# ultrasonic-breakout-smd.net
KiCad netlist of a schematic drawn in EAGLE
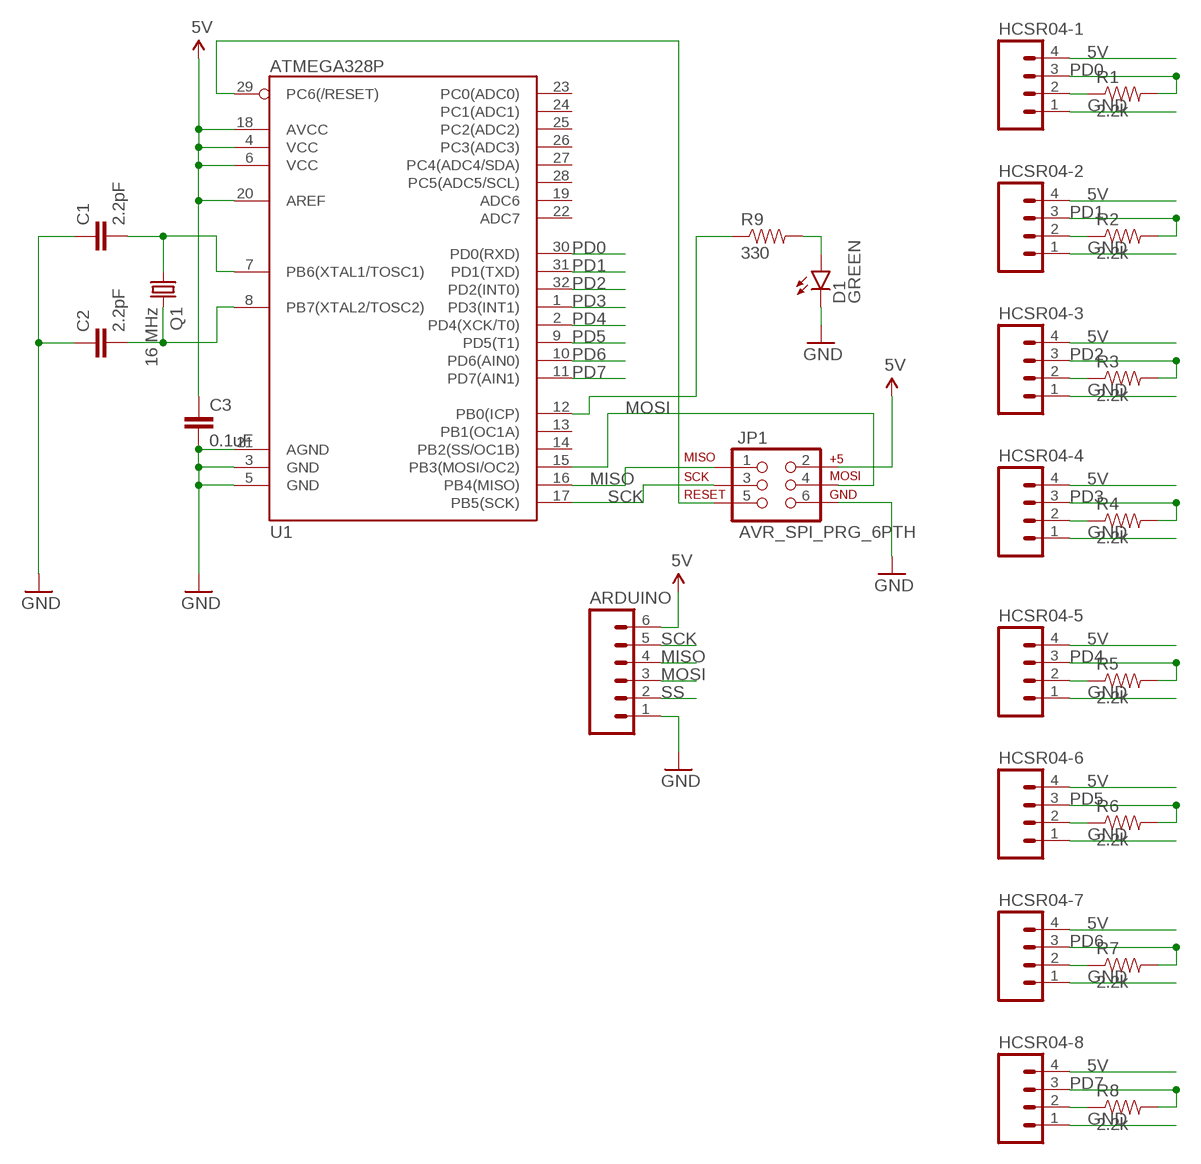
[diagram p0: schematic, sheet 1]

(export (version "E")
  (design (tool "Eeschema 10.0.6"))
  (components
    (comp (ref "ARDUINO")
      (value "M06LOCK")
      (footprint "eagle-import:1X06_LOCK")
      (libsource (lib "eagle-import") (part "M06LOCK"))
    )
    (comp (ref "C1")
      (value "2.2pF")
      (footprint "eagle-import:0402-CAP")
      (libsource (lib "eagle-import") (part "CAP0402-CAP"))
    )
    (comp (ref "C2")
      (value "2.2pF")
      (footprint "eagle-import:0402-CAP")
      (libsource (lib "eagle-import") (part "CAP0402-CAP"))
    )
    (comp (ref "C3")
      (value "0.1uF")
      (footprint "eagle-import:0402-CAP")
      (libsource (lib "eagle-import") (part "CAP0402-CAP"))
    )
    (comp (ref "D1")
      (value "GREEN")
      (footprint "eagle-import:LED-0603")
      (libsource (lib "eagle-import") (part "LED-GREEN0603"))
    )
    (comp (ref "HCSR04-1")
      (value "M04PTH")
      (footprint "eagle-import:1X04")
      (libsource (lib "eagle-import") (part "M04PTH"))
    )
    (comp (ref "HCSR04-2")
      (value "M04PTH")
      (footprint "eagle-import:1X04")
      (libsource (lib "eagle-import") (part "M04PTH"))
    )
    (comp (ref "HCSR04-3")
      (value "M04PTH")
      (footprint "eagle-import:1X04")
      (libsource (lib "eagle-import") (part "M04PTH"))
    )
    (comp (ref "HCSR04-4")
      (value "M04PTH")
      (footprint "eagle-import:1X04")
      (libsource (lib "eagle-import") (part "M04PTH"))
    )
    (comp (ref "HCSR04-5")
      (value "M04PTH")
      (footprint "eagle-import:1X04")
      (libsource (lib "eagle-import") (part "M04PTH"))
    )
    (comp (ref "HCSR04-6")
      (value "M04PTH")
      (footprint "eagle-import:1X04")
      (libsource (lib "eagle-import") (part "M04PTH"))
    )
    (comp (ref "HCSR04-7")
      (value "M04PTH")
      (footprint "eagle-import:1X04")
      (libsource (lib "eagle-import") (part "M04PTH"))
    )
    (comp (ref "HCSR04-8")
      (value "M04PTH")
      (footprint "eagle-import:1X04")
      (libsource (lib "eagle-import") (part "M04PTH"))
    )
    (comp (ref "JP1")
      (value "AVR_SPI_PRG_6PTH")
      (footprint "eagle-import:2X3")
      (libsource (lib "eagle-import") (part "AVR_SPI_PRG_6PTH"))
    )
    (comp (ref "Q1")
      (value "16 MHz")
      (footprint "eagle-import:HC49U-V")
      (libsource (lib "eagle-import") (part "CRYSTALHC49U-V"))
    )
    (comp (ref "R1")
      (value "2.2k")
      (footprint "eagle-import:0402-RES")
      (libsource (lib "eagle-import") (part "RESISTOR0402-RES"))
    )
    (comp (ref "R2")
      (value "2.2k")
      (footprint "eagle-import:0402-RES")
      (libsource (lib "eagle-import") (part "RESISTOR0402-RES"))
    )
    (comp (ref "R3")
      (value "2.2k")
      (footprint "eagle-import:0402-RES")
      (libsource (lib "eagle-import") (part "RESISTOR0402-RES"))
    )
    (comp (ref "R4")
      (value "2.2k")
      (footprint "eagle-import:0402-RES")
      (libsource (lib "eagle-import") (part "RESISTOR0402-RES"))
    )
    (comp (ref "R5")
      (value "2.2k")
      (footprint "eagle-import:0402-RES")
      (libsource (lib "eagle-import") (part "RESISTOR0402-RES"))
    )
    (comp (ref "R6")
      (value "2.2k")
      (footprint "eagle-import:0402-RES")
      (libsource (lib "eagle-import") (part "RESISTOR0402-RES"))
    )
    (comp (ref "R7")
      (value "2.2k")
      (footprint "eagle-import:0402-RES")
      (libsource (lib "eagle-import") (part "RESISTOR0402-RES"))
    )
    (comp (ref "R8")
      (value "2.2k")
      (footprint "eagle-import:0402-RES")
      (libsource (lib "eagle-import") (part "RESISTOR0402-RES"))
    )
    (comp (ref "R9")
      (value "330")
      (footprint "eagle-import:0402-RES")
      (libsource (lib "eagle-import") (part "RESISTOR0402-RES"))
    )
    (comp (ref "U1")
      (value "ATMEGA328P")
      (footprint "eagle-import:TQFP32-08")
      (libsource (lib "eagle-import") (part "ATMEGA328_SMT"))
    )
  )
  (nets
    (net (code "1") (name "/MISO") (class "Default")
      (node (ref "ARDUINO") (pin "4") (pinfunction "4_4") (pintype "passive"))
      (node (ref "JP1") (pin "1") (pinfunction "1_1") (pintype "passive"))
      (node (ref "U1") (pin "16") (pinfunction "PB4(MISO)_16") (pintype "bidirectional"))
    )
    (net (code "2") (name "/MOSI") (class "Default")
      (node (ref "ARDUINO") (pin "3") (pinfunction "3_3") (pintype "passive"))
      (node (ref "JP1") (pin "4") (pinfunction "4_4") (pintype "passive"))
      (node (ref "U1") (pin "15") (pinfunction "PB3(MOSI/OC2)_15") (pintype "bidirectional"))
    )
    (net (code "3") (name "/PD0") (class "Default")
      (node (ref "HCSR04-1") (pin "3") (pinfunction "3_3") (pintype "passive"))
      (node (ref "R1") (pin "2") (pinfunction "2_2") (pintype "passive"))
      (node (ref "U1") (pin "30") (pinfunction "PD0(RXD)_30") (pintype "bidirectional"))
    )
    (net (code "4") (name "/PD1") (class "Default")
      (node (ref "HCSR04-2") (pin "3") (pinfunction "3_3") (pintype "passive"))
      (node (ref "R2") (pin "2") (pinfunction "2_2") (pintype "passive"))
      (node (ref "U1") (pin "31") (pinfunction "PD1(TXD)_31") (pintype "bidirectional"))
    )
    (net (code "5") (name "/PD2") (class "Default")
      (node (ref "HCSR04-3") (pin "3") (pinfunction "3_3") (pintype "passive"))
      (node (ref "R3") (pin "2") (pinfunction "2_2") (pintype "passive"))
      (node (ref "U1") (pin "32") (pinfunction "PD2(INT0)_32") (pintype "bidirectional"))
    )
    (net (code "6") (name "/PD3") (class "Default")
      (node (ref "HCSR04-4") (pin "3") (pinfunction "3_3") (pintype "passive"))
      (node (ref "R4") (pin "2") (pinfunction "2_2") (pintype "passive"))
      (node (ref "U1") (pin "1") (pinfunction "PD3(INT1)_1") (pintype "bidirectional"))
    )
    (net (code "7") (name "/PD4") (class "Default")
      (node (ref "HCSR04-5") (pin "3") (pinfunction "3_3") (pintype "passive"))
      (node (ref "R5") (pin "2") (pinfunction "2_2") (pintype "passive"))
      (node (ref "U1") (pin "2") (pinfunction "PD4(XCK/T0)_2") (pintype "bidirectional"))
    )
    (net (code "8") (name "/PD5") (class "Default")
      (node (ref "HCSR04-6") (pin "3") (pinfunction "3_3") (pintype "passive"))
      (node (ref "R6") (pin "2") (pinfunction "2_2") (pintype "passive"))
      (node (ref "U1") (pin "9") (pinfunction "PD5(T1)_9") (pintype "bidirectional"))
    )
    (net (code "9") (name "/PD6") (class "Default")
      (node (ref "HCSR04-7") (pin "3") (pinfunction "3_3") (pintype "passive"))
      (node (ref "R7") (pin "2") (pinfunction "2_2") (pintype "passive"))
      (node (ref "U1") (pin "10") (pinfunction "PD6(AIN0)_10") (pintype "bidirectional"))
    )
    (net (code "10") (name "/PD7") (class "Default")
      (node (ref "HCSR04-8") (pin "3") (pinfunction "3_3") (pintype "passive"))
      (node (ref "R8") (pin "2") (pinfunction "2_2") (pintype "passive"))
      (node (ref "U1") (pin "11") (pinfunction "PD7(AIN1)_11") (pintype "bidirectional"))
    )
    (net (code "11") (name "/SCK") (class "Default")
      (node (ref "ARDUINO") (pin "5") (pinfunction "5_5") (pintype "passive"))
      (node (ref "JP1") (pin "3") (pinfunction "3_3") (pintype "passive"))
      (node (ref "U1") (pin "17") (pinfunction "PB5(SCK)_17") (pintype "bidirectional"))
    )
    (net (code "12") (name "/SS") (class "Default")
      (node (ref "ARDUINO") (pin "2") (pinfunction "2_2") (pintype "passive"))
    )
    (net (code "13") (name "5V") (class "Default")
      (node (ref "ARDUINO") (pin "6") (pinfunction "6_6") (pintype "passive"))
      (node (ref "C3") (pin "1") (pinfunction "1_1") (pintype "passive"))
      (node (ref "HCSR04-1") (pin "4") (pinfunction "4_4") (pintype "passive"))
      (node (ref "HCSR04-2") (pin "4") (pinfunction "4_4") (pintype "passive"))
      (node (ref "HCSR04-3") (pin "4") (pinfunction "4_4") (pintype "passive"))
      (node (ref "HCSR04-4") (pin "4") (pinfunction "4_4") (pintype "passive"))
      (node (ref "HCSR04-5") (pin "4") (pinfunction "4_4") (pintype "passive"))
      (node (ref "HCSR04-6") (pin "4") (pinfunction "4_4") (pintype "passive"))
      (node (ref "HCSR04-7") (pin "4") (pinfunction "4_4") (pintype "passive"))
      (node (ref "HCSR04-8") (pin "4") (pinfunction "4_4") (pintype "passive"))
      (node (ref "JP1") (pin "2") (pinfunction "2_2") (pintype "passive"))
      (node (ref "U1") (pin "18") (pinfunction "AVCC_18") (pintype "bidirectional"))
      (node (ref "U1") (pin "20") (pinfunction "AREF_20") (pintype "bidirectional"))
      (node (ref "U1") (pin "4") (pinfunction "VCC_4") (pintype "bidirectional"))
      (node (ref "U1") (pin "6") (pinfunction "VCC_6") (pintype "bidirectional"))
    )
    (net (code "14") (name "GND") (class "Default")
      (node (ref "ARDUINO") (pin "1") (pinfunction "1_1") (pintype "passive"))
      (node (ref "C1") (pin "1") (pinfunction "1_1") (pintype "passive"))
      (node (ref "C2") (pin "1") (pinfunction "1_1") (pintype "passive"))
      (node (ref "C3") (pin "2") (pinfunction "2_2") (pintype "passive"))
      (node (ref "D1") (pin "C") (pinfunction "C_C") (pintype "passive"))
      (node (ref "HCSR04-1") (pin "1") (pinfunction "1_1") (pintype "passive"))
      (node (ref "HCSR04-2") (pin "1") (pinfunction "1_1") (pintype "passive"))
      (node (ref "HCSR04-3") (pin "1") (pinfunction "1_1") (pintype "passive"))
      (node (ref "HCSR04-4") (pin "1") (pinfunction "1_1") (pintype "passive"))
      (node (ref "HCSR04-5") (pin "1") (pinfunction "1_1") (pintype "passive"))
      (node (ref "HCSR04-6") (pin "1") (pinfunction "1_1") (pintype "passive"))
      (node (ref "HCSR04-7") (pin "1") (pinfunction "1_1") (pintype "passive"))
      (node (ref "HCSR04-8") (pin "1") (pinfunction "1_1") (pintype "passive"))
      (node (ref "JP1") (pin "6") (pinfunction "6_6") (pintype "passive"))
      (node (ref "U1") (pin "21") (pinfunction "AGND_21") (pintype "bidirectional"))
      (node (ref "U1") (pin "3") (pinfunction "GND_3") (pintype "bidirectional"))
      (node (ref "U1") (pin "5") (pinfunction "GND_5") (pintype "bidirectional"))
    )
    (net (code "15") (name "Net-(D1-PadA)") (class "Default")
      (node (ref "D1") (pin "A") (pinfunction "A_A") (pintype "passive"))
      (node (ref "R9") (pin "2") (pinfunction "2_2") (pintype "passive"))
    )
    (net (code "16") (name "Net-(HCSR04-1-Pad2)") (class "Default")
      (node (ref "HCSR04-1") (pin "2") (pinfunction "2_2") (pintype "passive"))
      (node (ref "R1") (pin "1") (pinfunction "1_1") (pintype "passive"))
    )
    (net (code "17") (name "Net-(HCSR04-2-Pad2)") (class "Default")
      (node (ref "HCSR04-2") (pin "2") (pinfunction "2_2") (pintype "passive"))
      (node (ref "R2") (pin "1") (pinfunction "1_1") (pintype "passive"))
    )
    (net (code "18") (name "Net-(HCSR04-3-Pad2)") (class "Default")
      (node (ref "HCSR04-3") (pin "2") (pinfunction "2_2") (pintype "passive"))
      (node (ref "R3") (pin "1") (pinfunction "1_1") (pintype "passive"))
    )
    (net (code "19") (name "Net-(HCSR04-4-Pad2)") (class "Default")
      (node (ref "HCSR04-4") (pin "2") (pinfunction "2_2") (pintype "passive"))
      (node (ref "R4") (pin "1") (pinfunction "1_1") (pintype "passive"))
    )
    (net (code "20") (name "Net-(HCSR04-5-Pad2)") (class "Default")
      (node (ref "HCSR04-5") (pin "2") (pinfunction "2_2") (pintype "passive"))
      (node (ref "R5") (pin "1") (pinfunction "1_1") (pintype "passive"))
    )
    (net (code "21") (name "Net-(HCSR04-6-Pad2)") (class "Default")
      (node (ref "HCSR04-6") (pin "2") (pinfunction "2_2") (pintype "passive"))
      (node (ref "R6") (pin "1") (pinfunction "1_1") (pintype "passive"))
    )
    (net (code "22") (name "Net-(HCSR04-7-Pad2)") (class "Default")
      (node (ref "HCSR04-7") (pin "2") (pinfunction "2_2") (pintype "passive"))
      (node (ref "R7") (pin "1") (pinfunction "1_1") (pintype "passive"))
    )
    (net (code "23") (name "Net-(HCSR04-8-Pad2)") (class "Default")
      (node (ref "HCSR04-8") (pin "2") (pinfunction "2_2") (pintype "passive"))
      (node (ref "R8") (pin "1") (pinfunction "1_1") (pintype "passive"))
    )
    (net (code "24") (name "Net-(U1-PB0(ICP))") (class "Default")
      (node (ref "R9") (pin "1") (pinfunction "1_1") (pintype "passive"))
      (node (ref "U1") (pin "12") (pinfunction "PB0(ICP)_12") (pintype "bidirectional"))
    )
    (net (code "25") (name "Net-(U1-PB6(XTAL1{slash}TOSC1))") (class "Default")
      (node (ref "C1") (pin "2") (pinfunction "2_2") (pintype "passive"))
      (node (ref "Q1") (pin "1") (pinfunction "1_1") (pintype "passive"))
      (node (ref "U1") (pin "7") (pinfunction "PB6(XTAL1/TOSC1)_7") (pintype "bidirectional"))
    )
    (net (code "26") (name "Net-(U1-PB7(XTAL2{slash}TOSC2))") (class "Default")
      (node (ref "C2") (pin "2") (pinfunction "2_2") (pintype "passive"))
      (node (ref "Q1") (pin "2") (pinfunction "2_2") (pintype "passive"))
      (node (ref "U1") (pin "8") (pinfunction "PB7(XTAL2/TOSC2)_8") (pintype "bidirectional"))
    )
    (net (code "27") (name "Net-(U1-PC6({slash}RESET))") (class "Default")
      (node (ref "JP1") (pin "5") (pinfunction "5_5") (pintype "passive"))
      (node (ref "U1") (pin "29") (pinfunction "PC6(/RESET)_29") (pintype "bidirectional"))
    )
    (net (code "28") (name "unconnected-(U1-ADC6-Pad19)") (class "Default")
      (node (ref "U1") (pin "19") (pinfunction "ADC6_19") (pintype "bidirectional"))
    )
    (net (code "29") (name "unconnected-(U1-ADC7-Pad22)") (class "Default")
      (node (ref "U1") (pin "22") (pinfunction "ADC7_22") (pintype "bidirectional"))
    )
    (net (code "30") (name "unconnected-(U1-PB1(OC1A)-Pad13)") (class "Default")
      (node (ref "U1") (pin "13") (pinfunction "PB1(OC1A)_13") (pintype "bidirectional"))
    )
    (net (code "31") (name "unconnected-(U1-PB2(SS{slash}OC1B)-Pad14)") (class "Default")
      (node (ref "U1") (pin "14") (pinfunction "PB2(SS/OC1B)_14") (pintype "bidirectional"))
    )
    (net (code "32") (name "unconnected-(U1-PC0(ADC0)-Pad23)") (class "Default")
      (node (ref "U1") (pin "23") (pinfunction "PC0(ADC0)_23") (pintype "bidirectional"))
    )
    (net (code "33") (name "unconnected-(U1-PC1(ADC1)-Pad24)") (class "Default")
      (node (ref "U1") (pin "24") (pinfunction "PC1(ADC1)_24") (pintype "bidirectional"))
    )
    (net (code "34") (name "unconnected-(U1-PC2(ADC2)-Pad25)") (class "Default")
      (node (ref "U1") (pin "25") (pinfunction "PC2(ADC2)_25") (pintype "bidirectional"))
    )
    (net (code "35") (name "unconnected-(U1-PC3(ADC3)-Pad26)") (class "Default")
      (node (ref "U1") (pin "26") (pinfunction "PC3(ADC3)_26") (pintype "bidirectional"))
    )
    (net (code "36") (name "unconnected-(U1-PC4(ADC4{slash}SDA)-Pad27)") (class "Default")
      (node (ref "U1") (pin "27") (pinfunction "PC4(ADC4/SDA)_27") (pintype "bidirectional"))
    )
    (net (code "37") (name "unconnected-(U1-PC5(ADC5{slash}SCL)-Pad28)") (class "Default")
      (node (ref "U1") (pin "28") (pinfunction "PC5(ADC5/SCL)_28") (pintype "bidirectional"))
    )
  )
)
